# watchPogoSerial.net
KiCad netlist of a schematic drawn in EAGLE
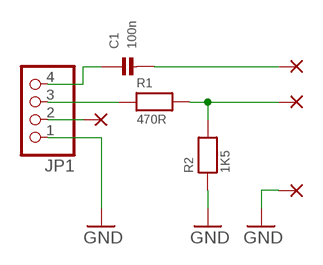
[diagram p0: schematic, sheet 1]

(export (version "E")
  (design (tool "Eeschema 10.0.6"))
  (components
    (comp (ref "C1")
      (value "100n")
      (footprint "eagle-import:0805")
      (libsource (lib "eagle-import") (part "CAP_CERAMIC0805"))
    )
    (comp (ref "JP1")
      (value "PINHD-1X4")
      (footprint "eagle-import:1X04")
      (libsource (lib "eagle-import") (part "PINHD-1X4"))
    )
    (comp (ref "PAD1")
      (value "PAD0.8-LRG")
      (footprint "eagle-import:PAD-0.8-LRG")
      (libsource (lib "eagle-import") (part "PAD0.8-LRG"))
    )
    (comp (ref "PAD3")
      (value "PAD0.8-LRG")
      (footprint "eagle-import:PAD-0.8-LRG")
      (libsource (lib "eagle-import") (part "PAD0.8-LRG"))
    )
    (comp (ref "PAD6")
      (value "PAD0.8-LRG")
      (footprint "eagle-import:PAD-0.8-LRG")
      (libsource (lib "eagle-import") (part "PAD0.8-LRG"))
    )
    (comp (ref "PAD12")
      (value "PAD0.8-LRG")
      (footprint "eagle-import:PAD-0.8-LRG")
      (libsource (lib "eagle-import") (part "PAD0.8-LRG"))
    )
    (comp (ref "R1")
      (value "470R")
      (footprint "eagle-import:0805")
      (libsource (lib "eagle-import") (part "RESISTOR0805"))
    )
    (comp (ref "R2")
      (value "1K5")
      (footprint "eagle-import:0805")
      (libsource (lib "eagle-import") (part "RESISTOR0805"))
    )
  )
  (nets
    (net (code "1") (name "GND") (class "Default")
      (node (ref "JP1") (pin "1") (pinfunction "1_1") (pintype "passive"))
      (node (ref "PAD1") (pin "P$1") (pinfunction "P$1_P$1") (pintype "passive"))
      (node (ref "R2") (pin "1") (pinfunction "1_1") (pintype "passive"))
    )
    (net (code "2") (name "Net-(C1-P$1)") (class "Default")
      (node (ref "C1") (pin "1") (pinfunction "P$1_1") (pintype "passive"))
      (node (ref "JP1") (pin "4") (pinfunction "4_4") (pintype "passive"))
    )
    (net (code "3") (name "Net-(C1-P$2)") (class "Default")
      (node (ref "C1") (pin "2") (pinfunction "P$2_2") (pintype "passive"))
      (node (ref "PAD3") (pin "P$1") (pinfunction "P$1_P$1") (pintype "passive"))
    )
    (net (code "4") (name "Net-(JP1-Pad2)") (class "Default")
      (node (ref "JP1") (pin "2") (pinfunction "2_2") (pintype "passive"))
      (node (ref "PAD12") (pin "P$1") (pinfunction "P$1_P$1") (pintype "passive"))
    )
    (net (code "5") (name "Net-(JP1-Pad3)") (class "Default")
      (node (ref "JP1") (pin "3") (pinfunction "3_3") (pintype "passive"))
      (node (ref "R1") (pin "1") (pinfunction "1_1") (pintype "passive"))
    )
    (net (code "6") (name "Net-(PAD6-PadP$1)") (class "Default")
      (node (ref "PAD6") (pin "P$1") (pinfunction "P$1_P$1") (pintype "passive"))
      (node (ref "R1") (pin "2") (pinfunction "2_2") (pintype "passive"))
      (node (ref "R2") (pin "2") (pinfunction "2_2") (pintype "passive"))
    )
  )
)
